# STM8S003F3P6_Board_Ver1.net
KiCad netlist of a schematic drawn in Altium Designer
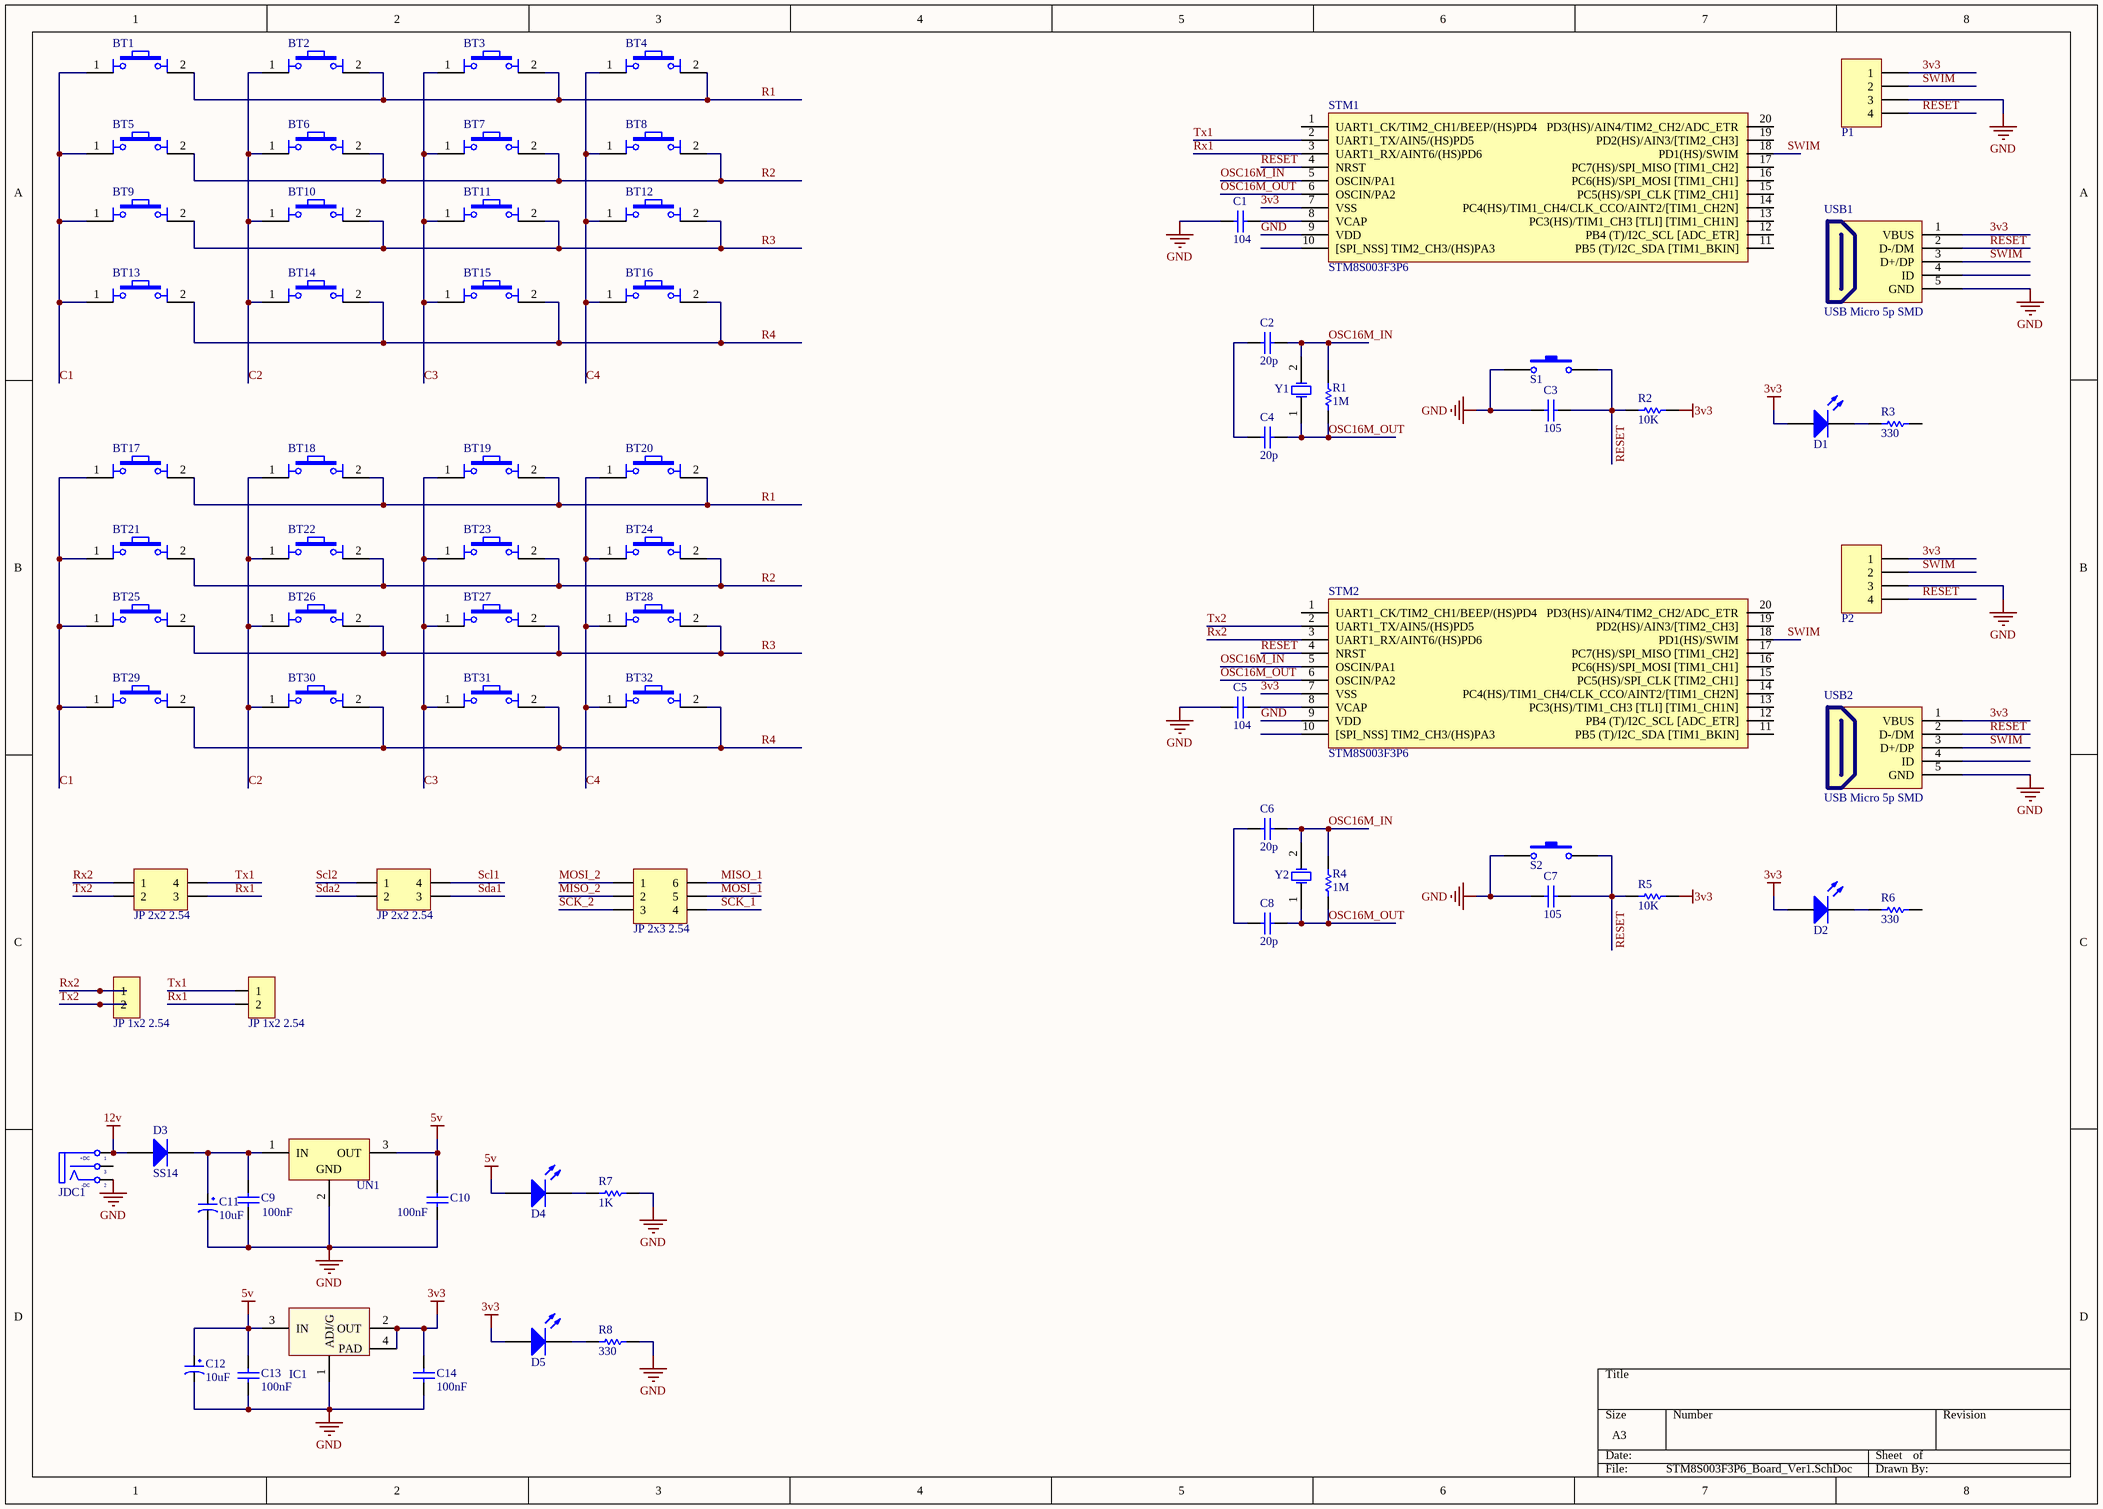
[diagram p0: STM8S003F3P6_Board_Ver1.SchDoc]

(export (version "E")
  (design (tool "Eeschema 10.0.6"))
  (components
    (comp (ref "BT1")
      (value "Nut Nhan 4 Chan Cam 6x6")
      (footprint "Nut Nhan 4 Chan Cam 6x6")
      (description "Nut Nhan 4 Chan 6x6mm")
      (libsource (lib "Altium_Lib_by_KhueNguyenCreator") (part "Nut Nhan 4 Chan Cam 6x6"))
    )
    (comp (ref "BT2")
      (value "Nut Nhan 4 Chan Cam 6x6")
      (footprint "Nut Nhan 4 Chan Cam 6x6")
      (description "Nut Nhan 4 Chan 6x6mm")
      (libsource (lib "Altium_Lib_by_KhueNguyenCreator") (part "Nut Nhan 4 Chan Cam 6x6"))
    )
    (comp (ref "BT3")
      (value "Nut Nhan 4 Chan Cam 6x6")
      (footprint "Nut Nhan 4 Chan Cam 6x6")
      (description "Nut Nhan 4 Chan 6x6mm")
      (libsource (lib "Altium_Lib_by_KhueNguyenCreator") (part "Nut Nhan 4 Chan Cam 6x6"))
    )
    (comp (ref "BT4")
      (value "Nut Nhan 4 Chan Cam 6x6")
      (footprint "Nut Nhan 4 Chan Cam 6x6")
      (description "Nut Nhan 4 Chan 6x6mm")
      (libsource (lib "Altium_Lib_by_KhueNguyenCreator") (part "Nut Nhan 4 Chan Cam 6x6"))
    )
    (comp (ref "BT5")
      (value "Nut Nhan 4 Chan Cam 6x6")
      (footprint "Nut Nhan 4 Chan Cam 6x6")
      (description "Nut Nhan 4 Chan 6x6mm")
      (libsource (lib "Altium_Lib_by_KhueNguyenCreator") (part "Nut Nhan 4 Chan Cam 6x6"))
    )
    (comp (ref "BT6")
      (value "Nut Nhan 4 Chan Cam 6x6")
      (footprint "Nut Nhan 4 Chan Cam 6x6")
      (description "Nut Nhan 4 Chan 6x6mm")
      (libsource (lib "Altium_Lib_by_KhueNguyenCreator") (part "Nut Nhan 4 Chan Cam 6x6"))
    )
    (comp (ref "BT7")
      (value "Nut Nhan 4 Chan Cam 6x6")
      (footprint "Nut Nhan 4 Chan Cam 6x6")
      (description "Nut Nhan 4 Chan 6x6mm")
      (libsource (lib "Altium_Lib_by_KhueNguyenCreator") (part "Nut Nhan 4 Chan Cam 6x6"))
    )
    (comp (ref "BT8")
      (value "Nut Nhan 4 Chan Cam 6x6")
      (footprint "Nut Nhan 4 Chan Cam 6x6")
      (description "Nut Nhan 4 Chan 6x6mm")
      (libsource (lib "Altium_Lib_by_KhueNguyenCreator") (part "Nut Nhan 4 Chan Cam 6x6"))
    )
    (comp (ref "BT9")
      (value "Nut Nhan 4 Chan Cam 6x6")
      (footprint "Nut Nhan 4 Chan Cam 6x6")
      (description "Nut Nhan 4 Chan 6x6mm")
      (libsource (lib "Altium_Lib_by_KhueNguyenCreator") (part "Nut Nhan 4 Chan Cam 6x6"))
    )
    (comp (ref "BT10")
      (value "Nut Nhan 4 Chan Cam 6x6")
      (footprint "Nut Nhan 4 Chan Cam 6x6")
      (description "Nut Nhan 4 Chan 6x6mm")
      (libsource (lib "Altium_Lib_by_KhueNguyenCreator") (part "Nut Nhan 4 Chan Cam 6x6"))
    )
    (comp (ref "BT11")
      (value "Nut Nhan 4 Chan Cam 6x6")
      (footprint "Nut Nhan 4 Chan Cam 6x6")
      (description "Nut Nhan 4 Chan 6x6mm")
      (libsource (lib "Altium_Lib_by_KhueNguyenCreator") (part "Nut Nhan 4 Chan Cam 6x6"))
    )
    (comp (ref "BT12")
      (value "Nut Nhan 4 Chan Cam 6x6")
      (footprint "Nut Nhan 4 Chan Cam 6x6")
      (description "Nut Nhan 4 Chan 6x6mm")
      (libsource (lib "Altium_Lib_by_KhueNguyenCreator") (part "Nut Nhan 4 Chan Cam 6x6"))
    )
    (comp (ref "BT13")
      (value "Nut Nhan 4 Chan Cam 6x6")
      (footprint "Nut Nhan 4 Chan Cam 6x6")
      (description "Nut Nhan 4 Chan 6x6mm")
      (libsource (lib "Altium_Lib_by_KhueNguyenCreator") (part "Nut Nhan 4 Chan Cam 6x6"))
    )
    (comp (ref "BT14")
      (value "Nut Nhan 4 Chan Cam 6x6")
      (footprint "Nut Nhan 4 Chan Cam 6x6")
      (description "Nut Nhan 4 Chan 6x6mm")
      (libsource (lib "Altium_Lib_by_KhueNguyenCreator") (part "Nut Nhan 4 Chan Cam 6x6"))
    )
    (comp (ref "BT15")
      (value "Nut Nhan 4 Chan Cam 6x6")
      (footprint "Nut Nhan 4 Chan Cam 6x6")
      (description "Nut Nhan 4 Chan 6x6mm")
      (libsource (lib "Altium_Lib_by_KhueNguyenCreator") (part "Nut Nhan 4 Chan Cam 6x6"))
    )
    (comp (ref "BT16")
      (value "Nut Nhan 4 Chan Cam 6x6")
      (footprint "Nut Nhan 4 Chan Cam 6x6")
      (description "Nut Nhan 4 Chan 6x6mm")
      (libsource (lib "Altium_Lib_by_KhueNguyenCreator") (part "Nut Nhan 4 Chan Cam 6x6"))
    )
    (comp (ref "BT17")
      (value "Nut Nhan 4 Chan Cam 6x6")
      (footprint "Nut Nhan 4 Chan Cam 6x6")
      (description "Nut Nhan 4 Chan 6x6mm")
      (libsource (lib "Altium_Lib_by_KhueNguyenCreator") (part "Nut Nhan 4 Chan Cam 6x6"))
    )
    (comp (ref "BT18")
      (value "Nut Nhan 4 Chan Cam 6x6")
      (footprint "Nut Nhan 4 Chan Cam 6x6")
      (description "Nut Nhan 4 Chan 6x6mm")
      (libsource (lib "Altium_Lib_by_KhueNguyenCreator") (part "Nut Nhan 4 Chan Cam 6x6"))
    )
    (comp (ref "BT19")
      (value "Nut Nhan 4 Chan Cam 6x6")
      (footprint "Nut Nhan 4 Chan Cam 6x6")
      (description "Nut Nhan 4 Chan 6x6mm")
      (libsource (lib "Altium_Lib_by_KhueNguyenCreator") (part "Nut Nhan 4 Chan Cam 6x6"))
    )
    (comp (ref "BT20")
      (value "Nut Nhan 4 Chan Cam 6x6")
      (footprint "Nut Nhan 4 Chan Cam 6x6")
      (description "Nut Nhan 4 Chan 6x6mm")
      (libsource (lib "Altium_Lib_by_KhueNguyenCreator") (part "Nut Nhan 4 Chan Cam 6x6"))
    )
    (comp (ref "BT21")
      (value "Nut Nhan 4 Chan Cam 6x6")
      (footprint "Nut Nhan 4 Chan Cam 6x6")
      (description "Nut Nhan 4 Chan 6x6mm")
      (libsource (lib "Altium_Lib_by_KhueNguyenCreator") (part "Nut Nhan 4 Chan Cam 6x6"))
    )
    (comp (ref "BT22")
      (value "Nut Nhan 4 Chan Cam 6x6")
      (footprint "Nut Nhan 4 Chan Cam 6x6")
      (description "Nut Nhan 4 Chan 6x6mm")
      (libsource (lib "Altium_Lib_by_KhueNguyenCreator") (part "Nut Nhan 4 Chan Cam 6x6"))
    )
    (comp (ref "BT23")
      (value "Nut Nhan 4 Chan Cam 6x6")
      (footprint "Nut Nhan 4 Chan Cam 6x6")
      (description "Nut Nhan 4 Chan 6x6mm")
      (libsource (lib "Altium_Lib_by_KhueNguyenCreator") (part "Nut Nhan 4 Chan Cam 6x6"))
    )
    (comp (ref "BT24")
      (value "Nut Nhan 4 Chan Cam 6x6")
      (footprint "Nut Nhan 4 Chan Cam 6x6")
      (description "Nut Nhan 4 Chan 6x6mm")
      (libsource (lib "Altium_Lib_by_KhueNguyenCreator") (part "Nut Nhan 4 Chan Cam 6x6"))
    )
    (comp (ref "BT25")
      (value "Nut Nhan 4 Chan Cam 6x6")
      (footprint "Nut Nhan 4 Chan Cam 6x6")
      (description "Nut Nhan 4 Chan 6x6mm")
      (libsource (lib "Altium_Lib_by_KhueNguyenCreator") (part "Nut Nhan 4 Chan Cam 6x6"))
    )
    (comp (ref "BT26")
      (value "Nut Nhan 4 Chan Cam 6x6")
      (footprint "Nut Nhan 4 Chan Cam 6x6")
      (description "Nut Nhan 4 Chan 6x6mm")
      (libsource (lib "Altium_Lib_by_KhueNguyenCreator") (part "Nut Nhan 4 Chan Cam 6x6"))
    )
    (comp (ref "BT27")
      (value "Nut Nhan 4 Chan Cam 6x6")
      (footprint "Nut Nhan 4 Chan Cam 6x6")
      (description "Nut Nhan 4 Chan 6x6mm")
      (libsource (lib "Altium_Lib_by_KhueNguyenCreator") (part "Nut Nhan 4 Chan Cam 6x6"))
    )
    (comp (ref "BT28")
      (value "Nut Nhan 4 Chan Cam 6x6")
      (footprint "Nut Nhan 4 Chan Cam 6x6")
      (description "Nut Nhan 4 Chan 6x6mm")
      (libsource (lib "Altium_Lib_by_KhueNguyenCreator") (part "Nut Nhan 4 Chan Cam 6x6"))
    )
    (comp (ref "BT29")
      (value "Nut Nhan 4 Chan Cam 6x6")
      (footprint "Nut Nhan 4 Chan Cam 6x6")
      (description "Nut Nhan 4 Chan 6x6mm")
      (libsource (lib "Altium_Lib_by_KhueNguyenCreator") (part "Nut Nhan 4 Chan Cam 6x6"))
    )
    (comp (ref "BT30")
      (value "Nut Nhan 4 Chan Cam 6x6")
      (footprint "Nut Nhan 4 Chan Cam 6x6")
      (description "Nut Nhan 4 Chan 6x6mm")
      (libsource (lib "Altium_Lib_by_KhueNguyenCreator") (part "Nut Nhan 4 Chan Cam 6x6"))
    )
    (comp (ref "BT31")
      (value "Nut Nhan 4 Chan Cam 6x6")
      (footprint "Nut Nhan 4 Chan Cam 6x6")
      (description "Nut Nhan 4 Chan 6x6mm")
      (libsource (lib "Altium_Lib_by_KhueNguyenCreator") (part "Nut Nhan 4 Chan Cam 6x6"))
    )
    (comp (ref "BT32")
      (value "Nut Nhan 4 Chan Cam 6x6")
      (footprint "Nut Nhan 4 Chan Cam 6x6")
      (description "Nut Nhan 4 Chan 6x6mm")
      (libsource (lib "Altium_Lib_by_KhueNguyenCreator") (part "Nut Nhan 4 Chan Cam 6x6"))
    )
    (comp (ref "C1")
      (value "104")
      (footprint "tu 0805")
      (description "Dán")
      (libsource (lib "Altium_Lib_by_KhueNguyenCreator") (part "Tu 0805 104 50V 10%"))
    )
    (comp (ref "C2")
      (value "20p")
      (footprint "CAP-SM-0805")
      (description "Capacitor")
      (fields (field (name "Comment") "Cap Non-Pol SMD"))
      (libsource (lib "PIF_Library") (part "Cap Non-Pol SMD"))
    )
    (comp (ref "C3")
      (value "105")
      (footprint "CAP-SM-0805")
      (description "Capacitor")
      (fields (field (name "Comment") "Cap Non-Pol SMD"))
      (libsource (lib "PIF_Library") (part "Cap Non-Pol SMD"))
    )
    (comp (ref "C4")
      (value "20p")
      (footprint "CAP-SM-0805")
      (description "Capacitor")
      (fields (field (name "Comment") "Cap Non-Pol SMD"))
      (libsource (lib "PIF_Library") (part "Cap Non-Pol SMD"))
    )
    (comp (ref "C5")
      (value "104")
      (footprint "tu 0805")
      (description "Dán")
      (libsource (lib "Altium_Lib_by_KhueNguyenCreator") (part "Tu 0805 104 50V 10%"))
    )
    (comp (ref "C6")
      (value "20p")
      (footprint "CAP-SM-0805")
      (description "Capacitor")
      (fields (field (name "Comment") "Cap Non-Pol SMD"))
      (libsource (lib "PIF_Library") (part "Cap Non-Pol SMD"))
    )
    (comp (ref "C7")
      (value "105")
      (footprint "CAP-SM-0805")
      (description "Capacitor")
      (fields (field (name "Comment") "Cap Non-Pol SMD"))
      (libsource (lib "PIF_Library") (part "Cap Non-Pol SMD"))
    )
    (comp (ref "C8")
      (value "20p")
      (footprint "CAP-SM-0805")
      (description "Capacitor")
      (fields (field (name "Comment") "Cap Non-Pol SMD"))
      (libsource (lib "PIF_Library") (part "Cap Non-Pol SMD"))
    )
    (comp (ref "C9")
      (value "100nF")
      (footprint "CAP-SM-0805")
      (description "Capacitor")
      (fields (field (name "Comment") "Cap Non-Pol SMD"))
      (libsource (lib "PIF_Library") (part "Cap Non-Pol SMD"))
    )
    (comp (ref "C10")
      (value "100nF")
      (footprint "CAP-SM-0805")
      (description "Capacitor")
      (fields (field (name "Comment") "Cap Non-Pol SMD"))
      (libsource (lib "PIF_Library") (part "Cap Non-Pol SMD"))
    )
    (comp (ref "C11")
      (value "10uF")
      (footprint "tu tantalum smd3216")
      (description "Dán")
      (libsource (lib "Altium_Lib_by_KhueNguyenCreator") (part "Tu tantalum 10uF 16V SMD3216"))
    )
    (comp (ref "C12")
      (value "10uF")
      (footprint "tu tantalum smd3216")
      (description "Dán")
      (libsource (lib "Altium_Lib_by_KhueNguyenCreator") (part "Tu tantalum 10uF 16V SMD3216"))
    )
    (comp (ref "C13")
      (value "100nF")
      (footprint "CAP-SM-0805")
      (description "Capacitor")
      (fields (field (name "Comment") "Cap Non-Pol SMD"))
      (libsource (lib "PIF_Library") (part "Cap Non-Pol SMD"))
    )
    (comp (ref "C14")
      (value "100nF")
      (footprint "CAP-SM-0805")
      (description "Capacitor")
      (fields (field (name "Comment") "Cap Non-Pol SMD"))
      (libsource (lib "PIF_Library") (part "Cap Non-Pol SMD"))
    )
    (comp (ref "D1")
      (value "LED SMD")
      (footprint "LED_0805_Blue")
      (description "LED")
      (libsource (lib "PIF_Library") (part "LED SMD"))
    )
    (comp (ref "D2")
      (value "LED SMD")
      (footprint "LED_0805_Blue")
      (description "LED")
      (libsource (lib "PIF_Library") (part "LED SMD"))
    )
    (comp (ref "D3")
      (value "SS14")
      (footprint "DIODE SMA")
      (description "Dán")
      (libsource (lib "Altium_Lib_by_KhueNguyenCreator") (part "Diode SS14 ( 1N5819)"))
    )
    (comp (ref "D4")
      (value "LED SMD")
      (footprint "LED_0805_Blue")
      (description "LED")
      (libsource (lib "PIF_Library") (part "LED SMD"))
    )
    (comp (ref "D5")
      (value "LED SMD")
      (footprint "LED_0805_Blue")
      (description "LED")
      (libsource (lib "PIF_Library") (part "LED SMD"))
    )
    (comp (ref "IC1")
      (value "LM1117")
      (footprint "SOT223-4N")
      (description "Available in 1.8V, 2.5V, 2.85V, 3.3V, 5V, and  Adjustable Versions")
      (libsource (lib "PIF_Library") (part "LM1117"))
    )
    (comp (ref "JDC1")
      (value "Jack DC")
      (footprint "DC-IN")
      (description "Jack DC input")
      (libsource (lib "PIF_Library") (part "Jack DC"))
    )
    (comp (ref "JP1")
      (value "JP 2x3 2.54")
      (footprint "JP 2x3 DT")
      (description "Cắm")
      (libsource (lib "Altium_Lib_by_KhueNguyenCreator") (part "JP 2x3 2.54 Duc Thang"))
    )
    (comp (ref "JP2")
      (value "JP 2x2 2.54")
      (footprint "JP 2x2 DT")
      (description "Cắm")
      (libsource (lib "Altium_Lib_by_KhueNguyenCreator") (part "JP 2x2 2.54 Duc Thang"))
    )
    (comp (ref "JP3")
      (value "JP 2x2 2.54")
      (footprint "JP 2x2 DT")
      (description "Cắm")
      (libsource (lib "Altium_Lib_by_KhueNguyenCreator") (part "JP 2x2 2.54 Duc Thang"))
    )
    (comp (ref "JP4")
      (value "JP 1x2 2.54")
      (footprint "JP 1x2 DT")
      (description "Cắm")
      (libsource (lib "Altium_Lib_by_KhueNguyenCreator") (part "JP 1x2 2.54 Duc Thang"))
    )
    (comp (ref "JP5")
      (value "JP 1x2 2.54")
      (footprint "JP 1x2 DT")
      (description "Cắm")
      (libsource (lib "Altium_Lib_by_KhueNguyenCreator") (part "JP 1x2 2.54 Duc Thang"))
    )
    (comp (ref "P1")
      (value "Header 4")
      (footprint "JP4")
      (description "Header, 4-Pin")
      (fields (field (name "PUBLISHER") "Altium Limited"))
      (libsource (lib "PIF_Library") (part "Header 4"))
    )
    (comp (ref "P2")
      (value "Header 4")
      (footprint "JP4")
      (description "Header, 4-Pin")
      (fields (field (name "PUBLISHER") "Altium Limited"))
      (libsource (lib "PIF_Library") (part "Header 4"))
    )
    (comp (ref "R1")
      (value "1M")
      (footprint "RES-SM-0805")
      (description "Resistor")
      (fields (field (name "Comment") "RESISTOR SMD"))
      (libsource (lib "PIF_Library") (part "RESISTOR SMD"))
    )
    (comp (ref "R2")
      (value "10K")
      (footprint "RES-SM-0805")
      (description "Resistor")
      (fields (field (name "Comment") "RESISTOR SMD"))
      (libsource (lib "PIF_Library") (part "RESISTOR SMD"))
    )
    (comp (ref "R3")
      (value "330")
      (footprint "RES-SM-0805")
      (description "Resistor")
      (fields (field (name "Comment") "RESISTOR SMD"))
      (libsource (lib "PIF_Library") (part "RESISTOR SMD"))
    )
    (comp (ref "R4")
      (value "1M")
      (footprint "RES-SM-0805")
      (description "Resistor")
      (fields (field (name "Comment") "RESISTOR SMD"))
      (libsource (lib "PIF_Library") (part "RESISTOR SMD"))
    )
    (comp (ref "R5")
      (value "10K")
      (footprint "RES-SM-0805")
      (description "Resistor")
      (fields (field (name "Comment") "RESISTOR SMD"))
      (libsource (lib "PIF_Library") (part "RESISTOR SMD"))
    )
    (comp (ref "R6")
      (value "330")
      (footprint "RES-SM-0805")
      (description "Resistor")
      (fields (field (name "Comment") "RESISTOR SMD"))
      (libsource (lib "PIF_Library") (part "RESISTOR SMD"))
    )
    (comp (ref "R7")
      (value "1K")
      (footprint "RES-SM-0805")
      (description "Resistor")
      (fields (field (name "Comment") "RESISTOR SMD"))
      (libsource (lib "PIF_Library") (part "RESISTOR SMD"))
    )
    (comp (ref "R8")
      (value "330")
      (footprint "RES-SM-0805")
      (description "Resistor")
      (fields (field (name "Comment") "RESISTOR SMD"))
      (libsource (lib "PIF_Library") (part "RESISTOR SMD"))
    )
    (comp (ref "S1")
      (value "Tact SW - 2Pin")
      (footprint "SW-SMD")
      (description "Switch button 2 pin")
      (libsource (lib "PIF_Library") (part "Tact SW - 2Pin"))
    )
    (comp (ref "S2")
      (value "Tact SW - 2Pin")
      (footprint "SW-SMD")
      (description "Switch button 2 pin")
      (libsource (lib "PIF_Library") (part "Tact SW - 2Pin"))
    )
    (comp (ref "STM1")
      (value "STM8S003F3P6")
      (footprint "TSSOP20")
      (description "Dán")
      (libsource (lib "Altium_Lib_by_KhueNguyenCreator") (part "STM8S003F3"))
    )
    (comp (ref "STM2")
      (value "STM8S003F3P6")
      (footprint "TSSOP20")
      (description "Dán")
      (libsource (lib "Altium_Lib_by_KhueNguyenCreator") (part "STM8S003F3"))
    )
    (comp (ref "UN1")
      (value "LM7805")
      (footprint "QTO-220")
      (description "Positive Voltage Regulator")
      (libsource (lib "PIF_Library") (part "LM7805"))
    )
    (comp (ref "USB1")
      (value "USB Micro 5p SMD")
      (footprint "USB Micro 5p SMD")
      (description "USB Type B")
      (libsource (lib "Altium_Lib_by_KhueNguyenCreator") (part "USB Micro 5p SMD"))
    )
    (comp (ref "USB2")
      (value "USB Micro 5p SMD")
      (footprint "USB Micro 5p SMD")
      (description "USB Type B")
      (libsource (lib "Altium_Lib_by_KhueNguyenCreator") (part "USB Micro 5p SMD"))
    )
    (comp (ref "Y1")
      (value "XTAL")
      (footprint "XT2")
      (description "Crystal Oscillator")
      (fields (field (name "PUBLISHER") "Altium Limited"))
      (libsource (lib "PIF_Library") (part "XTAL"))
    )
    (comp (ref "Y2")
      (value "XTAL")
      (footprint "XT2")
      (description "Crystal Oscillator")
      (fields (field (name "PUBLISHER") "Altium Limited"))
      (libsource (lib "PIF_Library") (part "XTAL"))
    )
  )
  (nets
    (net (code "1") (name "/C1") (class "Default")
      (node (ref "BT1") (pin "1") (pintype "passive"))
      (node (ref "BT13") (pin "1") (pintype "passive"))
      (node (ref "BT17") (pin "1") (pintype "passive"))
      (node (ref "BT21") (pin "1") (pintype "passive"))
      (node (ref "BT25") (pin "1") (pintype "passive"))
      (node (ref "BT29") (pin "1") (pintype "passive"))
      (node (ref "BT5") (pin "1") (pintype "passive"))
      (node (ref "BT9") (pin "1") (pintype "passive"))
    )
    (net (code "2") (name "/C2") (class "Default")
      (node (ref "BT10") (pin "1") (pintype "passive"))
      (node (ref "BT14") (pin "1") (pintype "passive"))
      (node (ref "BT18") (pin "1") (pintype "passive"))
      (node (ref "BT2") (pin "1") (pintype "passive"))
      (node (ref "BT22") (pin "1") (pintype "passive"))
      (node (ref "BT26") (pin "1") (pintype "passive"))
      (node (ref "BT30") (pin "1") (pintype "passive"))
      (node (ref "BT6") (pin "1") (pintype "passive"))
    )
    (net (code "3") (name "/C3") (class "Default")
      (node (ref "BT11") (pin "1") (pintype "passive"))
      (node (ref "BT15") (pin "1") (pintype "passive"))
      (node (ref "BT19") (pin "1") (pintype "passive"))
      (node (ref "BT23") (pin "1") (pintype "passive"))
      (node (ref "BT27") (pin "1") (pintype "passive"))
      (node (ref "BT3") (pin "1") (pintype "passive"))
      (node (ref "BT31") (pin "1") (pintype "passive"))
      (node (ref "BT7") (pin "1") (pintype "passive"))
    )
    (net (code "4") (name "/C4") (class "Default")
      (node (ref "BT12") (pin "1") (pintype "passive"))
      (node (ref "BT16") (pin "1") (pintype "passive"))
      (node (ref "BT20") (pin "1") (pintype "passive"))
      (node (ref "BT24") (pin "1") (pintype "passive"))
      (node (ref "BT28") (pin "1") (pintype "passive"))
      (node (ref "BT32") (pin "1") (pintype "passive"))
      (node (ref "BT4") (pin "1") (pintype "passive"))
      (node (ref "BT8") (pin "1") (pintype "passive"))
    )
    (net (code "5") (name "/MISO_1") (class "Default")
      (node (ref "JP1") (pin "6") (pinfunction "6_6") (pintype "passive"))
    )
    (net (code "6") (name "/MISO_2") (class "Default")
      (node (ref "JP1") (pin "2") (pinfunction "2_2") (pintype "passive"))
    )
    (net (code "7") (name "/MOSI_1") (class "Default")
      (node (ref "JP1") (pin "5") (pinfunction "5_5") (pintype "passive"))
    )
    (net (code "8") (name "/MOSI_2") (class "Default")
      (node (ref "JP1") (pin "1") (pinfunction "1_1") (pintype "passive"))
    )
    (net (code "9") (name "/OSC16M_IN") (class "Default")
      (node (ref "C2") (pin "2") (pinfunction "2_2") (pintype "passive"))
      (node (ref "C6") (pin "2") (pinfunction "2_2") (pintype "passive"))
      (node (ref "R1") (pin "2") (pinfunction "2_2") (pintype "passive"))
      (node (ref "R4") (pin "2") (pinfunction "2_2") (pintype "passive"))
      (node (ref "STM1") (pin "5") (pinfunction "OSCIN/PA1_5") (pintype "passive"))
      (node (ref "STM2") (pin "5") (pinfunction "OSCIN/PA1_5") (pintype "passive"))
      (node (ref "Y1") (pin "2") (pinfunction "OSC2_2") (pintype "passive"))
      (node (ref "Y2") (pin "2") (pinfunction "OSC2_2") (pintype "passive"))
    )
    (net (code "10") (name "/OSC16M_OUT") (class "Default")
      (node (ref "C4") (pin "2") (pinfunction "2_2") (pintype "passive"))
      (node (ref "C8") (pin "2") (pinfunction "2_2") (pintype "passive"))
      (node (ref "R1") (pin "1") (pinfunction "1_1") (pintype "passive"))
      (node (ref "R4") (pin "1") (pinfunction "1_1") (pintype "passive"))
      (node (ref "STM1") (pin "6") (pinfunction "OSCIN/PA2_6") (pintype "passive"))
      (node (ref "STM2") (pin "6") (pinfunction "OSCIN/PA2_6") (pintype "passive"))
      (node (ref "Y1") (pin "1") (pinfunction "OSC1_1") (pintype "passive"))
      (node (ref "Y2") (pin "1") (pinfunction "OSC1_1") (pintype "passive"))
    )
    (net (code "11") (name "/R1") (class "Default")
      (node (ref "BT1") (pin "2") (pintype "passive"))
      (node (ref "BT17") (pin "2") (pintype "passive"))
      (node (ref "BT18") (pin "2") (pintype "passive"))
      (node (ref "BT19") (pin "2") (pintype "passive"))
      (node (ref "BT2") (pin "2") (pintype "passive"))
      (node (ref "BT20") (pin "2") (pintype "passive"))
      (node (ref "BT3") (pin "2") (pintype "passive"))
      (node (ref "BT4") (pin "2") (pintype "passive"))
    )
    (net (code "12") (name "/R2") (class "Default")
      (node (ref "BT21") (pin "2") (pintype "passive"))
      (node (ref "BT22") (pin "2") (pintype "passive"))
      (node (ref "BT23") (pin "2") (pintype "passive"))
      (node (ref "BT24") (pin "2") (pintype "passive"))
      (node (ref "BT5") (pin "2") (pintype "passive"))
      (node (ref "BT6") (pin "2") (pintype "passive"))
      (node (ref "BT7") (pin "2") (pintype "passive"))
      (node (ref "BT8") (pin "2") (pintype "passive"))
    )
    (net (code "13") (name "/R3") (class "Default")
      (node (ref "BT10") (pin "2") (pintype "passive"))
      (node (ref "BT11") (pin "2") (pintype "passive"))
      (node (ref "BT12") (pin "2") (pintype "passive"))
      (node (ref "BT25") (pin "2") (pintype "passive"))
      (node (ref "BT26") (pin "2") (pintype "passive"))
      (node (ref "BT27") (pin "2") (pintype "passive"))
      (node (ref "BT28") (pin "2") (pintype "passive"))
      (node (ref "BT9") (pin "2") (pintype "passive"))
    )
    (net (code "14") (name "/R4") (class "Default")
      (node (ref "BT13") (pin "2") (pintype "passive"))
      (node (ref "BT14") (pin "2") (pintype "passive"))
      (node (ref "BT15") (pin "2") (pintype "passive"))
      (node (ref "BT16") (pin "2") (pintype "passive"))
      (node (ref "BT29") (pin "2") (pintype "passive"))
      (node (ref "BT30") (pin "2") (pintype "passive"))
      (node (ref "BT31") (pin "2") (pintype "passive"))
      (node (ref "BT32") (pin "2") (pintype "passive"))
    )
    (net (code "15") (name "/RESET") (class "Default")
      (node (ref "C3") (pin "2") (pinfunction "2_2") (pintype "passive"))
      (node (ref "C7") (pin "2") (pinfunction "2_2") (pintype "passive"))
      (node (ref "P1") (pin "4") (pinfunction "4_4") (pintype "passive"))
      (node (ref "P2") (pin "4") (pinfunction "4_4") (pintype "passive"))
      (node (ref "R2") (pin "1") (pinfunction "1_1") (pintype "passive"))
      (node (ref "R5") (pin "1") (pinfunction "1_1") (pintype "passive"))
      (node (ref "S1") (pin "2") (pinfunction "2_2") (pintype "passive"))
      (node (ref "S2") (pin "2") (pinfunction "2_2") (pintype "passive"))
      (node (ref "STM1") (pin "4") (pinfunction "NRST_4") (pintype "passive"))
      (node (ref "STM2") (pin "4") (pinfunction "NRST_4") (pintype "passive"))
      (node (ref "USB1") (pin "2") (pinfunction "D-/DM_2") (pintype "passive"))
      (node (ref "USB2") (pin "2") (pinfunction "D-/DM_2") (pintype "passive"))
    )
    (net (code "16") (name "/Rx1") (class "Default")
      (node (ref "JP2") (pin "3") (pinfunction "3_3") (pintype "passive"))
      (node (ref "JP5") (pin "2") (pinfunction "2_2") (pintype "passive"))
      (node (ref "STM1") (pin "3") (pinfunction "UART1_RX/AINT6/(HS)PD6_3") (pintype "passive"))
    )
    (net (code "17") (name "/Rx2") (class "Default")
      (node (ref "JP2") (pin "1") (pinfunction "1_1") (pintype "passive"))
      (node (ref "JP4") (pin "1") (pinfunction "1_1") (pintype "passive"))
      (node (ref "STM2") (pin "3") (pinfunction "UART1_RX/AINT6/(HS)PD6_3") (pintype "passive"))
    )
    (net (code "18") (name "/SCK_1") (class "Default")
      (node (ref "JP1") (pin "4") (pinfunction "4_4") (pintype "passive"))
    )
    (net (code "19") (name "/SCK_2") (class "Default")
      (node (ref "JP1") (pin "3") (pinfunction "3_3") (pintype "passive"))
    )
    (net (code "20") (name "/SWIM") (class "Default")
      (node (ref "P1") (pin "2") (pinfunction "2_2") (pintype "passive"))
      (node (ref "P2") (pin "2") (pinfunction "2_2") (pintype "passive"))
      (node (ref "STM1") (pin "18") (pinfunction "PD1(HS)/SWIM_18") (pintype "passive"))
      (node (ref "STM2") (pin "18") (pinfunction "PD1(HS)/SWIM_18") (pintype "passive"))
      (node (ref "USB1") (pin "3") (pinfunction "D+/DP_3") (pintype "passive"))
      (node (ref "USB2") (pin "3") (pinfunction "D+/DP_3") (pintype "passive"))
    )
    (net (code "21") (name "/Scl1") (class "Default")
      (node (ref "JP3") (pin "4") (pinfunction "4_4") (pintype "passive"))
    )
    (net (code "22") (name "/Scl2") (class "Default")
      (node (ref "JP3") (pin "1") (pinfunction "1_1") (pintype "passive"))
    )
    (net (code "23") (name "/Sda1") (class "Default")
      (node (ref "JP3") (pin "3") (pinfunction "3_3") (pintype "passive"))
    )
    (net (code "24") (name "/Sda2") (class "Default")
      (node (ref "JP3") (pin "2") (pinfunction "2_2") (pintype "passive"))
    )
    (net (code "25") (name "/Tx1") (class "Default")
      (node (ref "JP2") (pin "4") (pinfunction "4_4") (pintype "passive"))
      (node (ref "JP5") (pin "1") (pinfunction "1_1") (pintype "passive"))
      (node (ref "STM1") (pin "2") (pinfunction "UART1_TX/AIN5/(HS)PD5_2") (pintype "passive"))
    )
    (net (code "26") (name "/Tx2") (class "Default")
      (node (ref "JP2") (pin "2") (pinfunction "2_2") (pintype "passive"))
      (node (ref "JP4") (pin "2") (pinfunction "2_2") (pintype "passive"))
      (node (ref "STM2") (pin "2") (pinfunction "UART1_TX/AIN5/(HS)PD5_2") (pintype "passive"))
    )
    (net (code "27") (name "3v3") (class "Default")
      (node (ref "C14") (pin "2") (pinfunction "2_2") (pintype "passive"))
      (node (ref "D1") (pin "1") (pinfunction "A_1") (pintype "passive"))
      (node (ref "D2") (pin "1") (pinfunction "A_1") (pintype "passive"))
      (node (ref "D5") (pin "1") (pinfunction "A_1") (pintype "passive"))
      (node (ref "IC1") (pin "2") (pinfunction "OUT_2") (pintype "passive"))
      (node (ref "IC1") (pin "4") (pinfunction "PAD_4") (pintype "passive"))
      (node (ref "P1") (pin "1") (pinfunction "1_1") (pintype "passive"))
      (node (ref "P2") (pin "1") (pinfunction "1_1") (pintype "passive"))
      (node (ref "R2") (pin "2") (pinfunction "2_2") (pintype "passive"))
      (node (ref "R5") (pin "2") (pinfunction "2_2") (pintype "passive"))
      (node (ref "STM1") (pin "7") (pinfunction "VSS_7") (pintype "passive"))
      (node (ref "STM2") (pin "7") (pinfunction "VSS_7") (pintype "passive"))
      (node (ref "USB1") (pin "1") (pinfunction "VBUS_1") (pintype "passive"))
      (node (ref "USB2") (pin "1") (pinfunction "VBUS_1") (pintype "passive"))
    )
    (net (code "28") (name "5v") (class "Default")
      (node (ref "C10") (pin "2") (pinfunction "2_2") (pintype "passive"))
      (node (ref "C12") (pin "1") (pinfunction "1_1") (pintype "passive"))
      (node (ref "C13") (pin "2") (pinfunction "2_2") (pintype "passive"))
      (node (ref "D4") (pin "1") (pinfunction "A_1") (pintype "passive"))
      (node (ref "IC1") (pin "3") (pinfunction "IN_3") (pintype "passive"))
      (node (ref "UN1") (pin "3") (pinfunction "OUT_3") (pintype "power_in"))
    )
    (net (code "29") (name "12v") (class "Default")
      (node (ref "D3") (pin "1") (pinfunction "A_1") (pintype "passive"))
      (node (ref "JDC1") (pin "1") (pinfunction "T_1") (pintype "passive"))
    )
    (net (code "30") (name "GND") (class "Default")
      (node (ref "C1") (pin "2") (pinfunction "2_2") (pintype "passive"))
      (node (ref "C10") (pin "1") (pinfunction "1_1") (pintype "passive"))
      (node (ref "C11") (pin "2") (pinfunction "2_2") (pintype "passive"))
      (node (ref "C12") (pin "2") (pinfunction "2_2") (pintype "passive"))
      (node (ref "C13") (pin "1") (pinfunction "1_1") (pintype "passive"))
      (node (ref "C14") (pin "1") (pinfunction "1_1") (pintype "passive"))
      (node (ref "C3") (pin "1") (pinfunction "1_1") (pintype "passive"))
      (node (ref "C5") (pin "2") (pinfunction "2_2") (pintype "passive"))
      (node (ref "C7") (pin "1") (pinfunction "1_1") (pintype "passive"))
      (node (ref "C9") (pin "1") (pinfunction "1_1") (pintype "passive"))
      (node (ref "IC1") (pin "1") (pinfunction "ADJ/G_1") (pintype "passive"))
      (node (ref "JDC1") (pin "2") (pinfunction "TN_2") (pintype "passive"))
      (node (ref "P1") (pin "3") (pinfunction "3_3") (pintype "passive"))
      (node (ref "P2") (pin "3") (pinfunction "3_3") (pintype "passive"))
      (node (ref "R7") (pin "2") (pinfunction "2_2") (pintype "passive"))
      (node (ref "R8") (pin "2") (pinfunction "2_2") (pintype "passive"))
      (node (ref "S1") (pin "1") (pinfunction "1_1") (pintype "passive"))
      (node (ref "S2") (pin "1") (pinfunction "1_1") (pintype "passive"))
      (node (ref "STM1") (pin "9") (pinfunction "VDD_9") (pintype "passive"))
      (node (ref "STM2") (pin "9") (pinfunction "VDD_9") (pintype "passive"))
      (node (ref "UN1") (pin "2") (pinfunction "GND_2") (pintype "power_in"))
      (node (ref "USB1") (pin "5") (pinfunction "GND_5") (pintype "passive"))
      (node (ref "USB2") (pin "5") (pinfunction "GND_5") (pintype "passive"))
    )
    (net (code "31") (name "Net-(C2-Pad1)") (class "Default")
      (node (ref "C2") (pin "1") (pinfunction "1_1") (pintype "passive"))
      (node (ref "C4") (pin "1") (pinfunction "1_1") (pintype "passive"))
    )
    (net (code "32") (name "Net-(C6-Pad1)") (class "Default")
      (node (ref "C6") (pin "1") (pinfunction "1_1") (pintype "passive"))
      (node (ref "C8") (pin "1") (pinfunction "1_1") (pintype "passive"))
    )
    (net (code "33") (name "Net-(D1-K)") (class "Default")
      (node (ref "D1") (pin "2") (pinfunction "K_2") (pintype "passive"))
      (node (ref "R3") (pin "1") (pinfunction "1_1") (pintype "passive"))
    )
    (net (code "34") (name "Net-(D2-K)") (class "Default")
      (node (ref "D2") (pin "2") (pinfunction "K_2") (pintype "passive"))
      (node (ref "R6") (pin "1") (pinfunction "1_1") (pintype "passive"))
    )
    (net (code "35") (name "Net-(D3-K)") (class "Default")
      (node (ref "C11") (pin "1") (pinfunction "1_1") (pintype "passive"))
      (node (ref "C9") (pin "2") (pinfunction "2_2") (pintype "passive"))
      (node (ref "D3") (pin "2") (pinfunction "K_2") (pintype "passive"))
      (node (ref "UN1") (pin "1") (pinfunction "IN_1") (pintype "power_in"))
    )
    (net (code "36") (name "Net-(D4-K)") (class "Default")
      (node (ref "D4") (pin "2") (pinfunction "K_2") (pintype "passive"))
      (node (ref "R7") (pin "1") (pinfunction "1_1") (pintype "passive"))
    )
    (net (code "37") (name "Net-(D5-K)") (class "Default")
      (node (ref "D5") (pin "2") (pinfunction "K_2") (pintype "passive"))
      (node (ref "R8") (pin "1") (pinfunction "1_1") (pintype "passive"))
    )
    (net (code "38") (name "Net-(STM1-VCAP)") (class "Default")
      (node (ref "C1") (pin "1") (pinfunction "1_1") (pintype "passive"))
      (node (ref "STM1") (pin "8") (pinfunction "VCAP_8") (pintype "passive"))
    )
    (net (code "39") (name "Net-(STM2-VCAP)") (class "Default")
      (node (ref "C5") (pin "1") (pinfunction "1_1") (pintype "passive"))
      (node (ref "STM2") (pin "8") (pinfunction "VCAP_8") (pintype "passive"))
    )
    (net (code "40") (name "unconnected-(JDC1-S-Pad3)") (class "Default")
      (node (ref "JDC1") (pin "3") (pinfunction "S_3") (pintype "power_in"))
    )
    (net (code "41") (name "unconnected-(R3-Pad2)") (class "Default")
      (node (ref "R3") (pin "2") (pinfunction "2_2") (pintype "passive"))
    )
    (net (code "42") (name "unconnected-(R6-Pad2)") (class "Default")
      (node (ref "R6") (pin "2") (pinfunction "2_2") (pintype "passive"))
    )
    (net (code "43") (name "unconnected-(STM1-PB4_(T){slash}I2C_SCL_[ADC_ETR]-Pad12)") (class "Default")
      (node (ref "STM1") (pin "12") (pinfunction "PB4_(T)/I2C_SCL_[ADC_ETR]_12") (pintype "passive"))
    )
    (net (code "44") (name "unconnected-(STM1-PB5_(T){slash}I2C_SDA_[TIM1_BKIN]-Pad11)") (class "Default")
      (node (ref "STM1") (pin "11") (pinfunction "PB5_(T)/I2C_SDA_[TIM1_BKIN]_11") (pintype "passive"))
    )
    (net (code "45") (name "unconnected-(STM1-PC3(HS){slash}TIM1_CH3_[TLI]_[TIM1_CH1N]-Pad13)") (class "Default")
      (node (ref "STM1") (pin "13") (pinfunction "PC3(HS)/TIM1_CH3_[TLI]_[TIM1_CH1N]_13") (pintype "passive"))
    )
    (net (code "46") (name "unconnected-(STM1-PC4(HS){slash}TIM1_CH4{slash}CLK_CCO{slash}AINT2{slash}[TIM1_CH2N]-Pad14)") (class "Default")
      (node (ref "STM1") (pin "14") (pinfunction "PC4(HS)/TIM1_CH4/CLK_CCO/AINT2/[TIM1_CH2N]_14") (pintype "passive"))
    )
    (net (code "47") (name "unconnected-(STM1-PC5(HS){slash}SPI_CLK_[TIM2_CH1]-Pad15)") (class "Default")
      (node (ref "STM1") (pin "15") (pinfunction "PC5(HS)/SPI_CLK_[TIM2_CH1]_15") (pintype "passive"))
    )
    (net (code "48") (name "unconnected-(STM1-PC6(HS){slash}SPI_MOSI_[TIM1_CH1]-Pad16)") (class "Default")
      (node (ref "STM1") (pin "16") (pinfunction "PC6(HS)/SPI_MOSI_[TIM1_CH1]_16") (pintype "passive"))
    )
    (net (code "49") (name "unconnected-(STM1-PC7(HS){slash}SPI_MISO_[TIM1_CH2]-Pad17)") (class "Default")
      (node (ref "STM1") (pin "17") (pinfunction "PC7(HS)/SPI_MISO_[TIM1_CH2]_17") (pintype "passive"))
    )
    (net (code "50") (name "unconnected-(STM1-PD2(HS){slash}AIN3{slash}[TIM2_CH3]-Pad19)") (class "Default")
      (node (ref "STM1") (pin "19") (pinfunction "PD2(HS)/AIN3/[TIM2_CH3]_19") (pintype "passive"))
    )
    (net (code "51") (name "unconnected-(STM1-PD3(HS){slash}AIN4{slash}TIM2_CH2{slash}ADC_ETR-Pad20)") (class "Default")
      (node (ref "STM1") (pin "20") (pinfunction "PD3(HS)/AIN4/TIM2_CH2/ADC_ETR_20") (pintype "passive"))
    )
    (net (code "52") (name "unconnected-(STM1-UART1_CK{slash}TIM2_CH1{slash}BEEP{slash}(HS)PD4-Pad1)") (class "Default")
      (node (ref "STM1") (pin "1") (pinfunction "UART1_CK/TIM2_CH1/BEEP/(HS)PD4_1") (pintype "passive"))
    )
    (net (code "53") (name "unconnected-(STM1-[SPI_NSS]_TIM2_CH3{slash}(HS)PA3-Pad10)") (class "Default")
      (node (ref "STM1") (pin "10") (pinfunction "[SPI_NSS]_TIM2_CH3/(HS)PA3_10") (pintype "passive"))
    )
    (net (code "54") (name "unconnected-(STM2-PB4_(T){slash}I2C_SCL_[ADC_ETR]-Pad12)") (class "Default")
      (node (ref "STM2") (pin "12") (pinfunction "PB4_(T)/I2C_SCL_[ADC_ETR]_12") (pintype "passive"))
    )
    (net (code "55") (name "unconnected-(STM2-PB5_(T){slash}I2C_SDA_[TIM1_BKIN]-Pad11)") (class "Default")
      (node (ref "STM2") (pin "11") (pinfunction "PB5_(T)/I2C_SDA_[TIM1_BKIN]_11") (pintype "passive"))
    )
    (net (code "56") (name "unconnected-(STM2-PC3(HS){slash}TIM1_CH3_[TLI]_[TIM1_CH1N]-Pad13)") (class "Default")
      (node (ref "STM2") (pin "13") (pinfunction "PC3(HS)/TIM1_CH3_[TLI]_[TIM1_CH1N]_13") (pintype "passive"))
    )
    (net (code "57") (name "unconnected-(STM2-PC4(HS){slash}TIM1_CH4{slash}CLK_CCO{slash}AINT2{slash}[TIM1_CH2N]-Pad14)") (class "Default")
      (node (ref "STM2") (pin "14") (pinfunction "PC4(HS)/TIM1_CH4/CLK_CCO/AINT2/[TIM1_CH2N]_14") (pintype "passive"))
    )
    (net (code "58") (name "unconnected-(STM2-PC5(HS){slash}SPI_CLK_[TIM2_CH1]-Pad15)") (class "Default")
      (node (ref "STM2") (pin "15") (pinfunction "PC5(HS)/SPI_CLK_[TIM2_CH1]_15") (pintype "passive"))
    )
    (net (code "59") (name "unconnected-(STM2-PC6(HS){slash}SPI_MOSI_[TIM1_CH1]-Pad16)") (class "Default")
      (node (ref "STM2") (pin "16") (pinfunction "PC6(HS)/SPI_MOSI_[TIM1_CH1]_16") (pintype "passive"))
    )
    (net (code "60") (name "unconnected-(STM2-PC7(HS){slash}SPI_MISO_[TIM1_CH2]-Pad17)") (class "Default")
      (node (ref "STM2") (pin "17") (pinfunction "PC7(HS)/SPI_MISO_[TIM1_CH2]_17") (pintype "passive"))
    )
    (net (code "61") (name "unconnected-(STM2-PD2(HS){slash}AIN3{slash}[TIM2_CH3]-Pad19)") (class "Default")
      (node (ref "STM2") (pin "19") (pinfunction "PD2(HS)/AIN3/[TIM2_CH3]_19") (pintype "passive"))
    )
    (net (code "62") (name "unconnected-(STM2-PD3(HS){slash}AIN4{slash}TIM2_CH2{slash}ADC_ETR-Pad20)") (class "Default")
      (node (ref "STM2") (pin "20") (pinfunction "PD3(HS)/AIN4/TIM2_CH2/ADC_ETR_20") (pintype "passive"))
    )
    (net (code "63") (name "unconnected-(STM2-UART1_CK{slash}TIM2_CH1{slash}BEEP{slash}(HS)PD4-Pad1)") (class "Default")
      (node (ref "STM2") (pin "1") (pinfunction "UART1_CK/TIM2_CH1/BEEP/(HS)PD4_1") (pintype "passive"))
    )
    (net (code "64") (name "unconnected-(STM2-[SPI_NSS]_TIM2_CH3{slash}(HS)PA3-Pad10)") (class "Default")
      (node (ref "STM2") (pin "10") (pinfunction "[SPI_NSS]_TIM2_CH3/(HS)PA3_10") (pintype "passive"))
    )
    (net (code "65") (name "unconnected-(USB1-ID-Pad4)") (class "Default")
      (node (ref "USB1") (pin "4") (pinfunction "ID_4") (pintype "passive"))
    )
    (net (code "66") (name "unconnected-(USB2-ID-Pad4)") (class "Default")
      (node (ref "USB2") (pin "4") (pinfunction "ID_4") (pintype "passive"))
    )
  )
)
